# Alimentation.net
KiCad netlist of a schematic drawn in Altium Designer
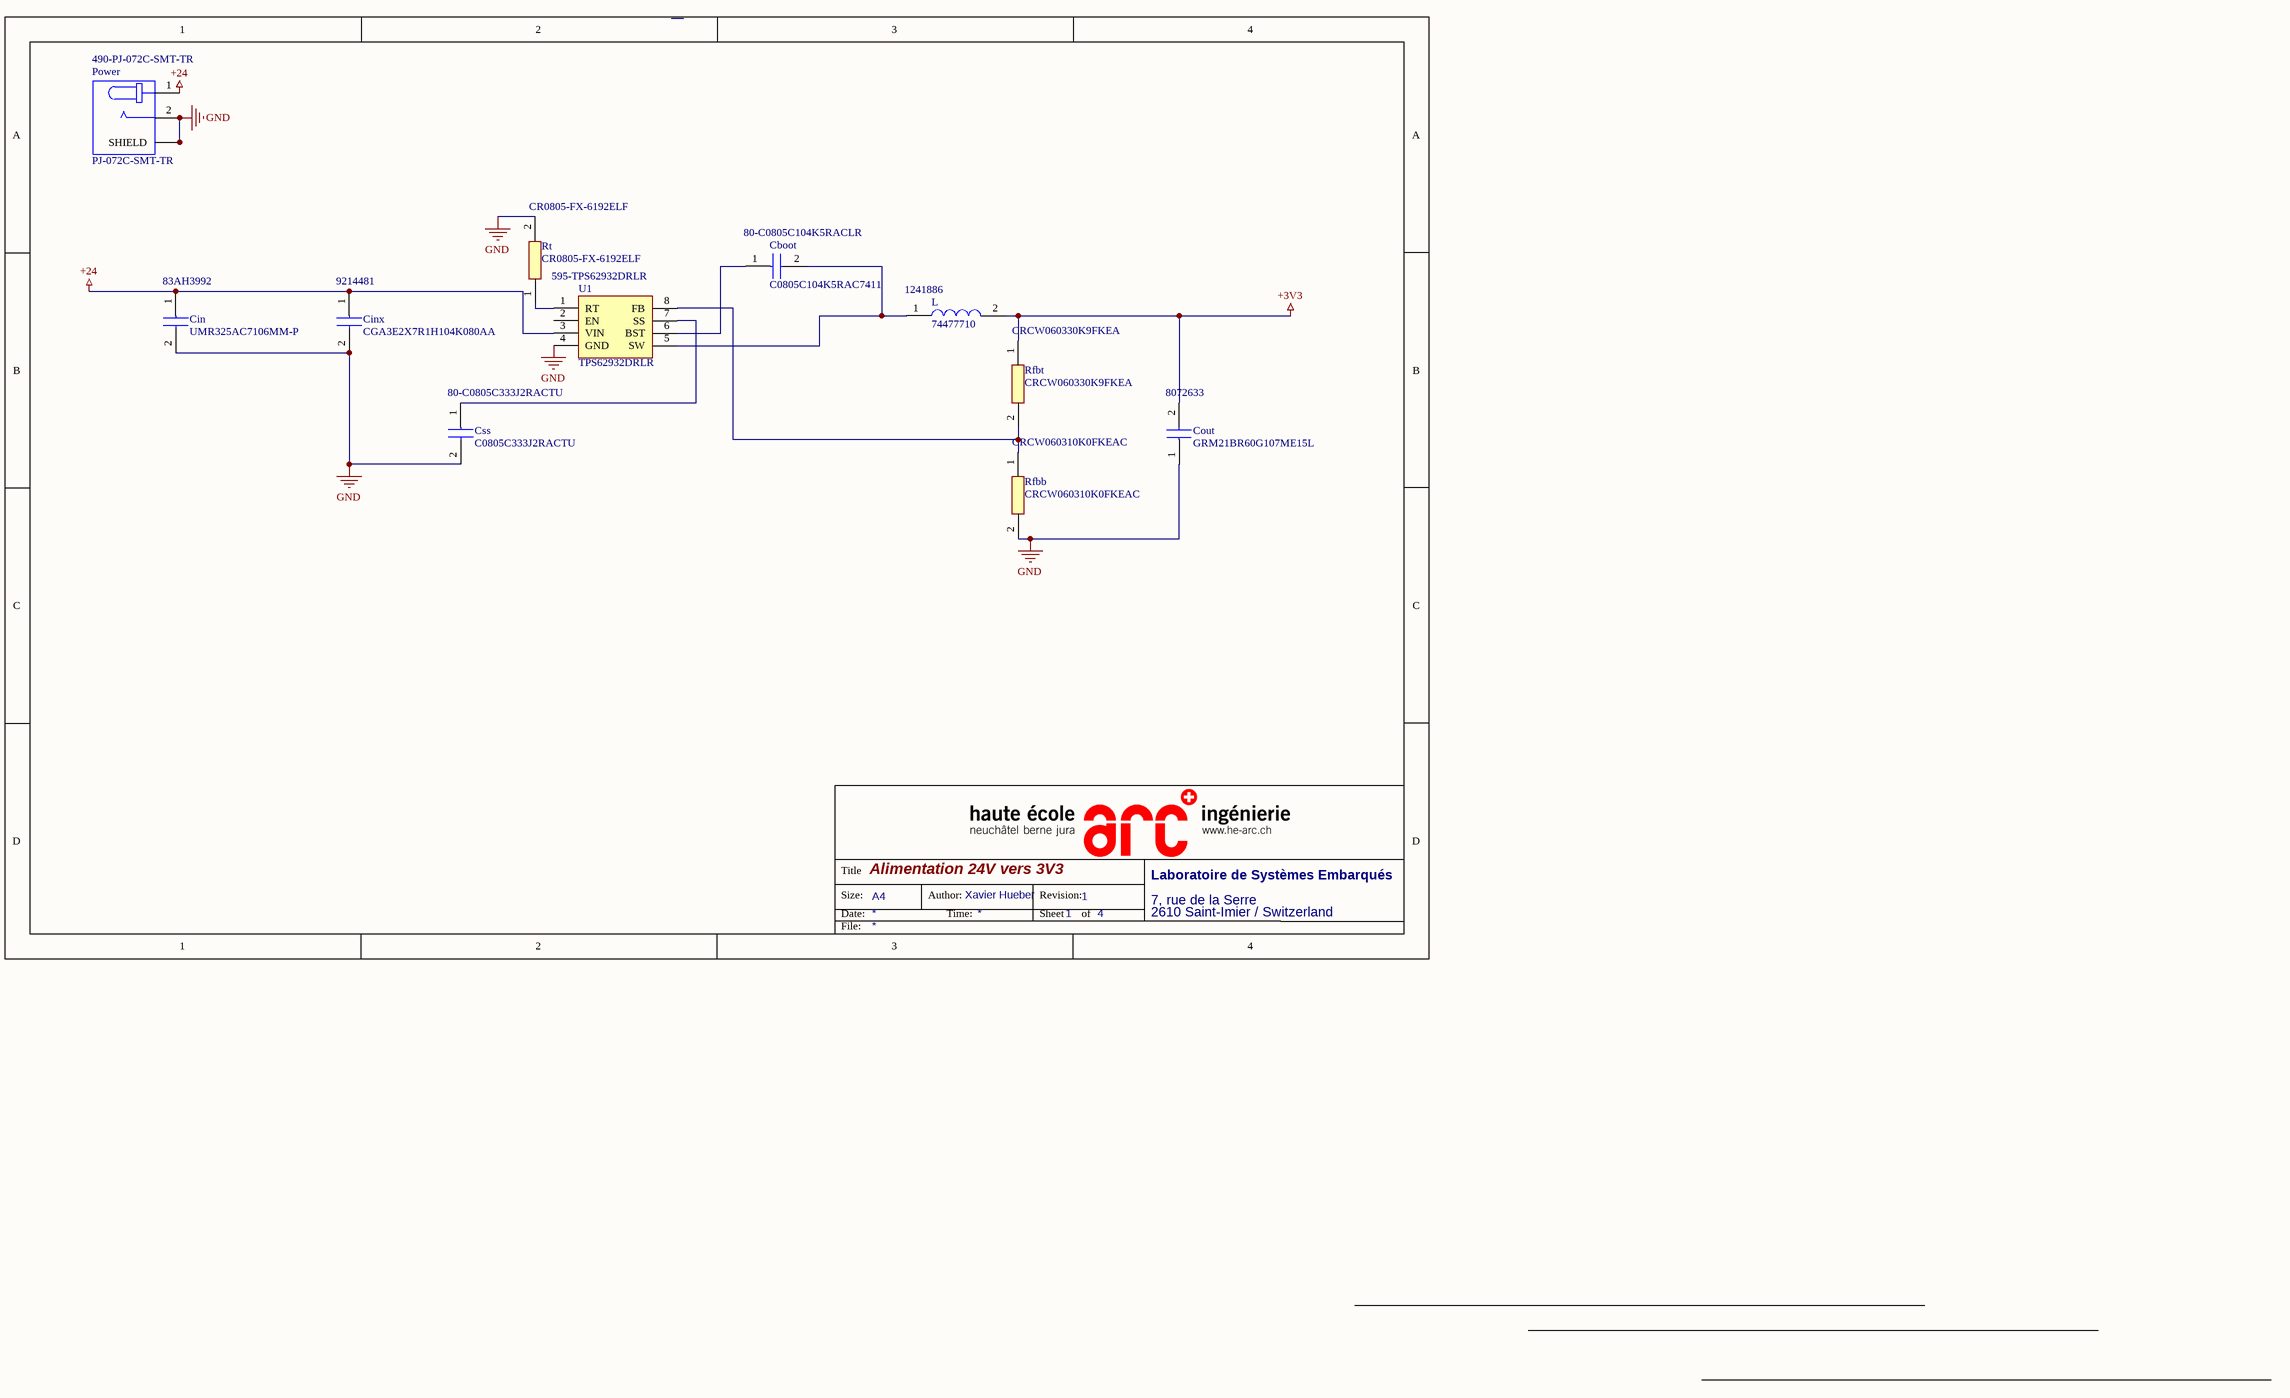
[diagram p0: Alimentation.SchDoc]

(export (version "E")
  (design (tool "Eeschema 10.0.6"))
  (components
    (comp (ref "Cboot")
      (value "C0805C104K5RAC7411")
      (footprint "SamacSys:CAPC2012X88N")
      (description "Multilayer Ceramic Capacitors MLCC - SMD/SMT 50V 0.1uF X7R 0805 10%")
      (fields
        (field (name "MOUSER2 PART NUMBER") "80-C0805C104K5RACLR")
        (field (name "SUPPLIER PART NUMBER 1") "80-C0805C104K5RACLR")
      )
      (libsource (lib "*") (part "C0805C104K5RAC7411"))
    )
    (comp (ref "Cin")
      (value "UMR325AC7106MM-P")
      (footprint "SamacSys:CAPC3225X280N")
      (description "Capacitor 1210 50V 10uF +-20%")
      (fields (field (name "SUPPLIER PART NUMBER 1") "83AH3992"))
      (libsource (lib "*") (part "UMR325AC7106MM-P"))
    )
    (comp (ref "Cinx")
      (value "CGA3E2X7R1H104K080AA")
      (footprint "SamacSys:CAPC1608X90N")
      (description "Capacitor 0603 100nF")
      (fields
        (field (name "MOUSER2 PART NUMBER") "810-CGA3E2X7R1H104K")
        (field (name "SUPPLIER PART NUMBER 1") "9214481")
      )
      (libsource (lib "*") (part "CGA3E2X7R1H104K080AA"))
    )
    (comp (ref "Cout")
      (value "GRM21BR60G107ME15L")
      (footprint "SamacSys:CAPC2012X145N")
      (description "0805 100 uF 4 V ±20% Tolerance X5R Multilayer Ceramic Chip Capacitor")
      (fields (field (name "SUPPLIER PART NUMBER 1") "8072633"))
      (libsource (lib "*") (part "GRM21BR60G107ME15L"))
    )
    (comp (ref "Css")
      (value "C0805C333J2RACTU")
      (footprint "SamacSys:C0805")
      (description "Multilayer Ceramic Capacitors MLCC - SMD/SMT 200V 0.033uF X7R 0805 5%")
      (fields (field (name "SUPPLIER PART NUMBER 1") "80-C0805C333J2RACTU"))
      (libsource (lib "*") (part "C0805C333J2RACTU"))
    )
    (comp (ref "L")
      (value "74477710")
      (footprint "74477710")
      (fields (field (name "SUPPLIER PART NUMBER 1") "1241886"))
      (libsource (lib "MesComposants") (part "74477710"))
    )
    (comp (ref "Power")
      (value "PJ-072C-SMT-TR")
      (footprint "PJ-072C-SMT-TR")
      (description "1.0 x 3.6 mm, 2.0 A, Horizontal, Surface Mount (SMT), Shielded, Dc Power Jack Connector")
      (fields (field (name "SUPPLIER PART NUMBER 1") "490-PJ-072C-SMT-TR"))
      (libsource (lib "MesComposants") (part "PJ-072C-SMT-TR"))
    )
    (comp (ref "Rfbb")
      (value "CRCW060310K0FKEAC")
      (footprint "SamacSys:RESC1608X55N")
      (description "Res Thick Film 0603 10K Ohm 1% 1/10W ±100ppm/°C Molded SMD Paper T/R")
      (fields
        (field (name "MOUSER2 PART NUMBER") "71-CRCW060310K0FKEAC")
        (field (name "SUPPLIER PART NUMBER 1") "CRCW060310K0FKEAC")
      )
      (libsource (lib "*") (part "CRCW060310K0FKEAC"))
    )
    (comp (ref "Rfbt")
      (value "CRCW060330K9FKEA")
      (footprint "SamacSys:RESC1608X50N")
      (description "Res Thick Film 0603 30.9K Ohm 1% 1/10W ±100ppm/°C Molded SMD SMD Paper T/R")
      (fields (field (name "SUPPLIER PART NUMBER 1") "CRCW060330K9FKEA"))
      (libsource (lib "*") (part "CRCW060330K9FKEA"))
    )
    (comp (ref "Rt")
      (value "CR0805-FX-6192ELF")
      (footprint "SamacSys:RESC2012X60N")
      (description "Resistor 0805 61.9kOhm")
      (fields (field (name "SUPPLIER PART NUMBER 1") "CR0805-FX-6192ELF"))
      (libsource (lib "*") (part "CR0805-FX-6192ELF"))
    )
    (comp (ref "U1")
      (value "TPS62932DRLR")
      (footprint "SamacSys:TPS62932DRLR")
      (description "3.8-V to 30-V input, 2-A, 200-kHz to 2.2-MHz, low-IQ synchronous buck converter in SOT-583 package")
      (fields (field (name "SUPPLIER PART NUMBER 1") "595-TPS62932DRLR"))
      (libsource (lib "*") (part "TPS62932DRLR"))
    )
  )
  (nets
    (net (code "1") (name "+3V3") (class "Default")
      (node (ref "Cout") (pin "2") (pinfunction "2_2") (pintype "passive"))
      (node (ref "L") (pin "2") (pinfunction "2_2") (pintype "passive"))
      (node (ref "Rfbt") (pin "1") (pinfunction "1_1") (pintype "passive"))
    )
    (net (code "2") (name "+24") (class "Default")
      (node (ref "Cin") (pin "1") (pinfunction "1_1") (pintype "passive"))
      (node (ref "Cinx") (pin "1") (pinfunction "1_1") (pintype "passive"))
      (node (ref "Power") (pin "1") (pinfunction "1_1") (pintype "passive"))
      (node (ref "U1") (pin "3") (pinfunction "VIN_3") (pintype "passive"))
    )
    (net (code "3") (name "GND") (class "Default")
      (node (ref "Cin") (pin "2") (pinfunction "2_2") (pintype "passive"))
      (node (ref "Cinx") (pin "2") (pinfunction "2_2") (pintype "passive"))
      (node (ref "Cout") (pin "1") (pinfunction "1_1") (pintype "passive"))
      (node (ref "Css") (pin "2") (pinfunction "2_2") (pintype "passive"))
      (node (ref "Power") (pin "2") (pinfunction "2_2") (pintype "passive"))
      (node (ref "Power") (pin "3") (pinfunction "SHIELD_3") (pintype "passive"))
      (node (ref "Power") (pin "4") (pinfunction "SHIELD_4") (pintype "passive"))
      (node (ref "Rfbb") (pin "2") (pinfunction "2_2") (pintype "passive"))
      (node (ref "Rt") (pin "2") (pinfunction "2_2") (pintype "passive"))
      (node (ref "U1") (pin "4") (pinfunction "GND_4") (pintype "passive"))
    )
    (net (code "4") (name "Net-(U1-BST)") (class "Default")
      (node (ref "Cboot") (pin "1") (pinfunction "1_1") (pintype "passive"))
      (node (ref "U1") (pin "6") (pinfunction "BST_6") (pintype "passive"))
    )
    (net (code "5") (name "Net-(U1-FB)") (class "Default")
      (node (ref "Rfbb") (pin "1") (pinfunction "1_1") (pintype "passive"))
      (node (ref "Rfbt") (pin "2") (pinfunction "2_2") (pintype "passive"))
      (node (ref "U1") (pin "8") (pinfunction "FB_8") (pintype "passive"))
    )
    (net (code "6") (name "Net-(U1-RT)") (class "Default")
      (node (ref "Rt") (pin "1") (pinfunction "1_1") (pintype "passive"))
      (node (ref "U1") (pin "1") (pinfunction "RT_1") (pintype "passive"))
    )
    (net (code "7") (name "Net-(U1-SS)") (class "Default")
      (node (ref "Css") (pin "1") (pinfunction "1_1") (pintype "passive"))
      (node (ref "U1") (pin "7") (pinfunction "SS_7") (pintype "passive"))
    )
    (net (code "8") (name "Net-(U1-SW)") (class "Default")
      (node (ref "Cboot") (pin "2") (pinfunction "2_2") (pintype "passive"))
      (node (ref "L") (pin "1") (pinfunction "1_1") (pintype "passive"))
      (node (ref "U1") (pin "5") (pinfunction "SW_5") (pintype "passive"))
    )
    (net (code "9") (name "unconnected-(U1-EN-Pad2)") (class "Default")
      (node (ref "U1") (pin "2") (pinfunction "EN_2") (pintype "passive"))
    )
  )
)
